# Sheet1.net
KiCad netlist of a schematic drawn in Altium Designer
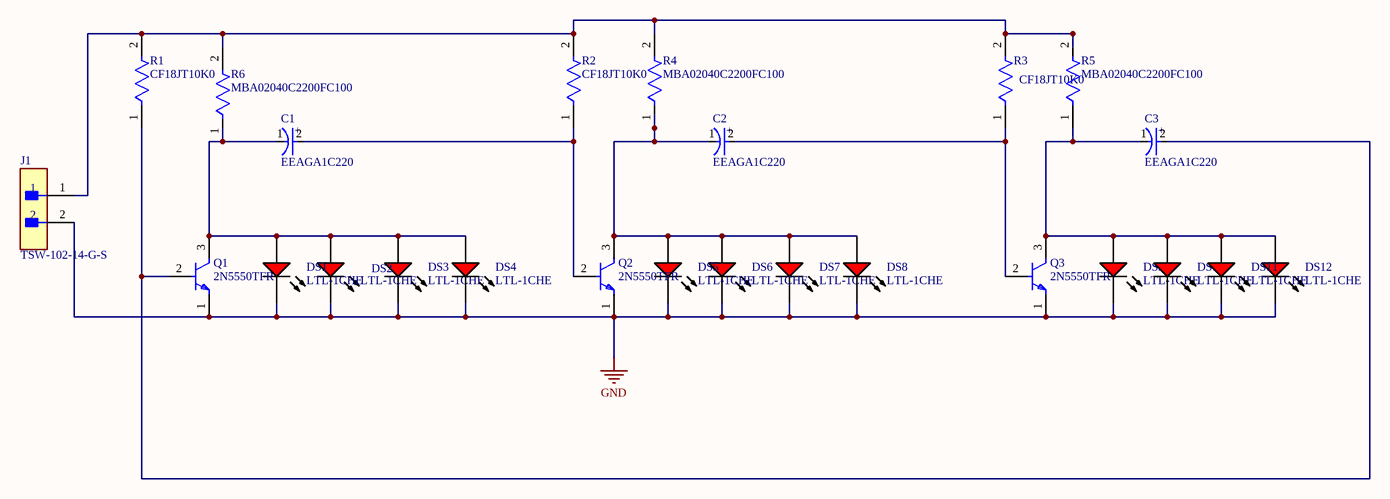
[diagram p0: Sheet1.SchDoc]

(export (version "E")
  (design (tool "Eeschema 10.0.6"))
  (components
    (comp (ref "C1")
      (value "EEAGA1C220")
      (footprint "FP-RAD-TH-D_5_0_5-L_7_1-F-MFG")
      (description "Aluminum Electrolytic Capacitors (Radial Lead Type) 22uF ±20% 16V")
      (fields (field (name "VOLTAGE") "16V") (field (name "TOLERANCE") "20%"))
      (libsource (lib "Altium Content Vault") (part "a00bbbee19879c290e62620ae7e47b1"))
    )
    (comp (ref "C2")
      (value "EEAGA1C220")
      (footprint "FP-RAD-TH-D_5_0_5-L_7_1-F-MFG")
      (description "Aluminum Electrolytic Capacitors (Radial Lead Type) 22uF ±20% 16V")
      (fields (field (name "VOLTAGE") "16V") (field (name "TOLERANCE") "20%"))
      (libsource (lib "Altium Content Vault") (part "a00bbbee19879c290e62620ae7e47b1"))
    )
    (comp (ref "C3")
      (value "EEAGA1C220")
      (footprint "FP-RAD-TH-D_5_0_5-L_7_1-F-MFG")
      (description "Aluminum Electrolytic Capacitors (Radial Lead Type) 22uF ±20% 16V")
      (fields (field (name "VOLTAGE") "16V") (field (name "TOLERANCE") "20%"))
      (libsource (lib "Altium Content Vault") (part "a00bbbee19879c290e62620ae7e47b1"))
    )
    (comp (ref "DS1")
      (value "LTL-1CHE")
      (footprint "INDPR60-254-520X380X650")
      (description "Radial LED, 12.6 mcd, 20 mA, 2 V, -55 to 100 degC, 2-Pin THD, RoHS, Bulk")
      (fields (field (name "TOLERANCE") "20%"))
      (libsource (lib "Altium Content Vault") (part "LED-RED-AK-2"))
    )
    (comp (ref "DS2")
      (value "LTL-1CHE")
      (footprint "INDPR60-254-520X380X650")
      (description "Radial LED, 12.6 mcd, 20 mA, 2 V, -55 to 100 degC, 2-Pin THD, RoHS, Bulk")
      (fields (field (name "TOLERANCE") "20%"))
      (libsource (lib "Altium Content Vault") (part "LED-RED-AK-2"))
    )
    (comp (ref "DS3")
      (value "LTL-1CHE")
      (footprint "INDPR60-254-520X380X650")
      (description "Radial LED, 12.6 mcd, 20 mA, 2 V, -55 to 100 degC, 2-Pin THD, RoHS, Bulk")
      (fields (field (name "TOLERANCE") "20%"))
      (libsource (lib "Altium Content Vault") (part "LED-RED-AK-2"))
    )
    (comp (ref "DS4")
      (value "LTL-1CHE")
      (footprint "INDPR60-254-520X380X650")
      (description "Radial LED, 12.6 mcd, 20 mA, 2 V, -55 to 100 degC, 2-Pin THD, RoHS, Bulk")
      (fields (field (name "TOLERANCE") "20%"))
      (libsource (lib "Altium Content Vault") (part "LED-RED-AK-2"))
    )
    (comp (ref "DS5")
      (value "LTL-1CHE")
      (footprint "INDPR60-254-520X380X650")
      (description "Radial LED, 12.6 mcd, 20 mA, 2 V, -55 to 100 degC, 2-Pin THD, RoHS, Bulk")
      (fields (field (name "TOLERANCE") "20%"))
      (libsource (lib "Altium Content Vault") (part "LED-RED-AK-2"))
    )
    (comp (ref "DS6")
      (value "LTL-1CHE")
      (footprint "INDPR60-254-520X380X650")
      (description "Radial LED, 12.6 mcd, 20 mA, 2 V, -55 to 100 degC, 2-Pin THD, RoHS, Bulk")
      (fields (field (name "TOLERANCE") "20%"))
      (libsource (lib "Altium Content Vault") (part "LED-RED-AK-2"))
    )
    (comp (ref "DS7")
      (value "LTL-1CHE")
      (footprint "INDPR60-254-520X380X650")
      (description "Radial LED, 12.6 mcd, 20 mA, 2 V, -55 to 100 degC, 2-Pin THD, RoHS, Bulk")
      (fields (field (name "TOLERANCE") "20%"))
      (libsource (lib "Altium Content Vault") (part "LED-RED-AK-2"))
    )
    (comp (ref "DS8")
      (value "LTL-1CHE")
      (footprint "INDPR60-254-520X380X650")
      (description "Radial LED, 12.6 mcd, 20 mA, 2 V, -55 to 100 degC, 2-Pin THD, RoHS, Bulk")
      (fields (field (name "TOLERANCE") "20%"))
      (libsource (lib "Altium Content Vault") (part "LED-RED-AK-2"))
    )
    (comp (ref "DS9")
      (value "LTL-1CHE")
      (footprint "INDPR60-254-520X380X650")
      (description "Radial LED, 12.6 mcd, 20 mA, 2 V, -55 to 100 degC, 2-Pin THD, RoHS, Bulk")
      (fields (field (name "TOLERANCE") "20%"))
      (libsource (lib "Altium Content Vault") (part "LED-RED-AK-2"))
    )
    (comp (ref "DS10")
      (value "LTL-1CHE")
      (footprint "INDPR60-254-520X380X650")
      (description "Radial LED, 12.6 mcd, 20 mA, 2 V, -55 to 100 degC, 2-Pin THD, RoHS, Bulk")
      (fields (field (name "TOLERANCE") "20%"))
      (libsource (lib "Altium Content Vault") (part "LED-RED-AK-2"))
    )
    (comp (ref "DS11")
      (value "LTL-1CHE")
      (footprint "INDPR60-254-520X380X650")
      (description "Radial LED, 12.6 mcd, 20 mA, 2 V, -55 to 100 degC, 2-Pin THD, RoHS, Bulk")
      (fields (field (name "TOLERANCE") "20%"))
      (libsource (lib "Altium Content Vault") (part "LED-RED-AK-2"))
    )
    (comp (ref "DS12")
      (value "LTL-1CHE")
      (footprint "INDPR60-254-520X380X650")
      (description "Radial LED, 12.6 mcd, 20 mA, 2 V, -55 to 100 degC, 2-Pin THD, RoHS, Bulk")
      (fields (field (name "TOLERANCE") "20%"))
      (libsource (lib "Altium Content Vault") (part "LED-RED-AK-2"))
    )
    (comp (ref "J1")
      (value "TSW-102-14-G-S")
      (footprint "FP-TSW-102-14-G-S-MFG")
      (description "CONN HEADER VERT 2POS 2.54MM")
      (libsource (lib "Altium Content Vault") (part "88c1139f9d239099ffebecbe3f7647a"))
    )
    (comp (ref "Q1")
      (value "2N5550TFR")
      (footprint "FP-135AR-MFG")
      (description "2N5550TFR Transistor, bjt, npn, 140V V(Br)Ceo, 600Ma I(C), to-92 Rohs Compliant: Yes")
      (libsource (lib "Altium Content Vault") (part "9e19cab19518d7a3085b4bde76cafd9"))
    )
    (comp (ref "Q2")
      (value "2N5550TFR")
      (footprint "FP-135AR-MFG")
      (description "2N5550TFR Transistor, bjt, npn, 140V V(Br)Ceo, 600Ma I(C), to-92 Rohs Compliant: Yes")
      (libsource (lib "Altium Content Vault") (part "9e19cab19518d7a3085b4bde76cafd9"))
    )
    (comp (ref "Q3")
      (value "2N5550TFR")
      (footprint "FP-135AR-MFG")
      (description "2N5550TFR Transistor, bjt, npn, 140V V(Br)Ceo, 600Ma I(C), to-92 Rohs Compliant: Yes")
      (libsource (lib "Altium Content Vault") (part "9e19cab19518d7a3085b4bde76cafd9"))
    )
    (comp (ref "R1")
      (value "CF18JT10K0")
      (footprint "FP-CF18-MFG")
      (description "RES 10K OHM 1/8W 5% CF AXIAL")
      (fields
        (field (name "MANUFACTURER") "Stackpole Electronics")
        (field (name "OCTOPART") "https://octopart.com/cf18jt10k0-stackpole+electronics-19205642")
      )
      (libsource (lib "Altium Content Vault") (part "1029c3af85768c4190bb7ad29bc67b5"))
    )
    (comp (ref "R2")
      (value "CF18JT10K0")
      (footprint "FP-CF18-MFG")
      (description "RES 10K OHM 1/8W 5% CF AXIAL")
      (fields
        (field (name "MANUFACTURER") "Stackpole Electronics")
        (field (name "OCTOPART") "https://octopart.com/cf18jt10k0-stackpole+electronics-19205642")
      )
      (libsource (lib "Altium Content Vault") (part "1029c3af85768c4190bb7ad29bc67b5"))
    )
    (comp (ref "R3")
      (value "CF18JT10K0")
      (footprint "FP-CF18-MFG")
      (description "RES 10K OHM 1/8W 5% CF AXIAL")
      (fields
        (field (name "MANUFACTURER") "Stackpole Electronics")
        (field (name "OCTOPART") "https://octopart.com/cf18jt10k0-stackpole+electronics-19205642")
      )
      (libsource (lib "Altium Content Vault") (part "1029c3af85768c4190bb7ad29bc67b5"))
    )
    (comp (ref "R4")
      (value "MBA02040C2200FC100")
      (footprint "FP-MBA0204-MFG")
      (description "RES 220 OHM 0.4W 1% AXIAL")
      (fields
        (field (name "OCTOPART") "https://octopart.com/mba02040c2200fc100-vishay-43743094")
        (field (name "MANUFACTURER") "Vishay BC Components")
      )
      (libsource (lib "Altium Content Vault") (part "1029c3af85768c4190bb7ad29bc67b5"))
    )
    (comp (ref "R5")
      (value "MBA02040C2200FC100")
      (footprint "FP-MBA0204-MFG")
      (description "RES 220 OHM 0.4W 1% AXIAL")
      (fields
        (field (name "OCTOPART") "https://octopart.com/mba02040c2200fc100-vishay-43743094")
        (field (name "MANUFACTURER") "Vishay BC Components")
      )
      (libsource (lib "Altium Content Vault") (part "1029c3af85768c4190bb7ad29bc67b5"))
    )
    (comp (ref "R6")
      (value "MBA02040C2200FC100")
      (footprint "FP-MBA0204-MFG")
      (description "RES 220 OHM 0.4W 1% AXIAL")
      (fields
        (field (name "OCTOPART") "https://octopart.com/mba02040c2200fc100-vishay-43743094")
        (field (name "MANUFACTURER") "Vishay BC Components")
      )
      (libsource (lib "Altium Content Vault") (part "1029c3af85768c4190bb7ad29bc67b5"))
    )
  )
  (nets
    (net (code "1") (name "GND") (class "Default")
      (node (ref "DS1") (pin "2") (pinfunction "K_2") (pintype "passive"))
      (node (ref "DS10") (pin "2") (pinfunction "K_2") (pintype "passive"))
      (node (ref "DS11") (pin "2") (pinfunction "K_2") (pintype "passive"))
      (node (ref "DS12") (pin "2") (pinfunction "K_2") (pintype "passive"))
      (node (ref "DS2") (pin "2") (pinfunction "K_2") (pintype "passive"))
      (node (ref "DS3") (pin "2") (pinfunction "K_2") (pintype "passive"))
      (node (ref "DS4") (pin "2") (pinfunction "K_2") (pintype "passive"))
      (node (ref "DS5") (pin "2") (pinfunction "K_2") (pintype "passive"))
      (node (ref "DS6") (pin "2") (pinfunction "K_2") (pintype "passive"))
      (node (ref "DS7") (pin "2") (pinfunction "K_2") (pintype "passive"))
      (node (ref "DS8") (pin "2") (pinfunction "K_2") (pintype "passive"))
      (node (ref "DS9") (pin "2") (pinfunction "K_2") (pintype "passive"))
      (node (ref "J1") (pin "2") (pinfunction "2_2") (pintype "passive"))
      (node (ref "Q1") (pin "1") (pinfunction "E_1") (pintype "passive"))
      (node (ref "Q2") (pin "1") (pinfunction "E_1") (pintype "passive"))
      (node (ref "Q3") (pin "1") (pinfunction "E_1") (pintype "passive"))
    )
    (net (code "2") (name "Net-(C1-A)") (class "Default")
      (node (ref "C1") (pin "2") (pinfunction "A_2") (pintype "passive"))
      (node (ref "Q2") (pin "2") (pinfunction "B_2") (pintype "passive"))
      (node (ref "R2") (pin "1") (pinfunction "1_1") (pintype "passive"))
    )
    (net (code "3") (name "Net-(C1-C)") (class "Default")
      (node (ref "C1") (pin "1") (pinfunction "C_1") (pintype "passive"))
      (node (ref "DS1") (pin "1") (pinfunction "A_1") (pintype "passive"))
      (node (ref "DS2") (pin "1") (pinfunction "A_1") (pintype "passive"))
      (node (ref "DS3") (pin "1") (pinfunction "A_1") (pintype "passive"))
      (node (ref "DS4") (pin "1") (pinfunction "A_1") (pintype "passive"))
      (node (ref "Q1") (pin "3") (pinfunction "C_3") (pintype "passive"))
      (node (ref "R6") (pin "1") (pinfunction "1_1") (pintype "passive"))
    )
    (net (code "4") (name "Net-(C2-A)") (class "Default")
      (node (ref "C2") (pin "2") (pinfunction "A_2") (pintype "passive"))
      (node (ref "Q3") (pin "2") (pinfunction "B_2") (pintype "passive"))
      (node (ref "R3") (pin "1") (pinfunction "1_1") (pintype "passive"))
    )
    (net (code "5") (name "Net-(C2-C)") (class "Default")
      (node (ref "C2") (pin "1") (pinfunction "C_1") (pintype "passive"))
      (node (ref "DS5") (pin "1") (pinfunction "A_1") (pintype "passive"))
      (node (ref "DS6") (pin "1") (pinfunction "A_1") (pintype "passive"))
      (node (ref "DS7") (pin "1") (pinfunction "A_1") (pintype "passive"))
      (node (ref "DS8") (pin "1") (pinfunction "A_1") (pintype "passive"))
      (node (ref "Q2") (pin "3") (pinfunction "C_3") (pintype "passive"))
      (node (ref "R4") (pin "1") (pinfunction "1_1") (pintype "passive"))
    )
    (net (code "6") (name "Net-(C3-A)") (class "Default")
      (node (ref "C3") (pin "2") (pinfunction "A_2") (pintype "passive"))
      (node (ref "Q1") (pin "2") (pinfunction "B_2") (pintype "passive"))
      (node (ref "R1") (pin "1") (pinfunction "1_1") (pintype "passive"))
    )
    (net (code "7") (name "Net-(C3-C)") (class "Default")
      (node (ref "C3") (pin "1") (pinfunction "C_1") (pintype "passive"))
      (node (ref "DS10") (pin "1") (pinfunction "A_1") (pintype "passive"))
      (node (ref "DS11") (pin "1") (pinfunction "A_1") (pintype "passive"))
      (node (ref "DS12") (pin "1") (pinfunction "A_1") (pintype "passive"))
      (node (ref "DS9") (pin "1") (pinfunction "A_1") (pintype "passive"))
      (node (ref "Q3") (pin "3") (pinfunction "C_3") (pintype "passive"))
      (node (ref "R5") (pin "1") (pinfunction "1_1") (pintype "passive"))
    )
    (net (code "8") (name "Net-(J1-Pad1)") (class "Default")
      (node (ref "J1") (pin "1") (pinfunction "1_1") (pintype "passive"))
      (node (ref "R1") (pin "2") (pinfunction "2_2") (pintype "passive"))
      (node (ref "R2") (pin "2") (pinfunction "2_2") (pintype "passive"))
      (node (ref "R3") (pin "2") (pinfunction "2_2") (pintype "passive"))
      (node (ref "R4") (pin "2") (pinfunction "2_2") (pintype "passive"))
      (node (ref "R5") (pin "2") (pinfunction "2_2") (pintype "passive"))
      (node (ref "R6") (pin "2") (pinfunction "2_2") (pintype "passive"))
    )
  )
)
